# umodular_brain8_arduino_mega_rev01.net
KiCad netlist of a schematic drawn in EAGLE
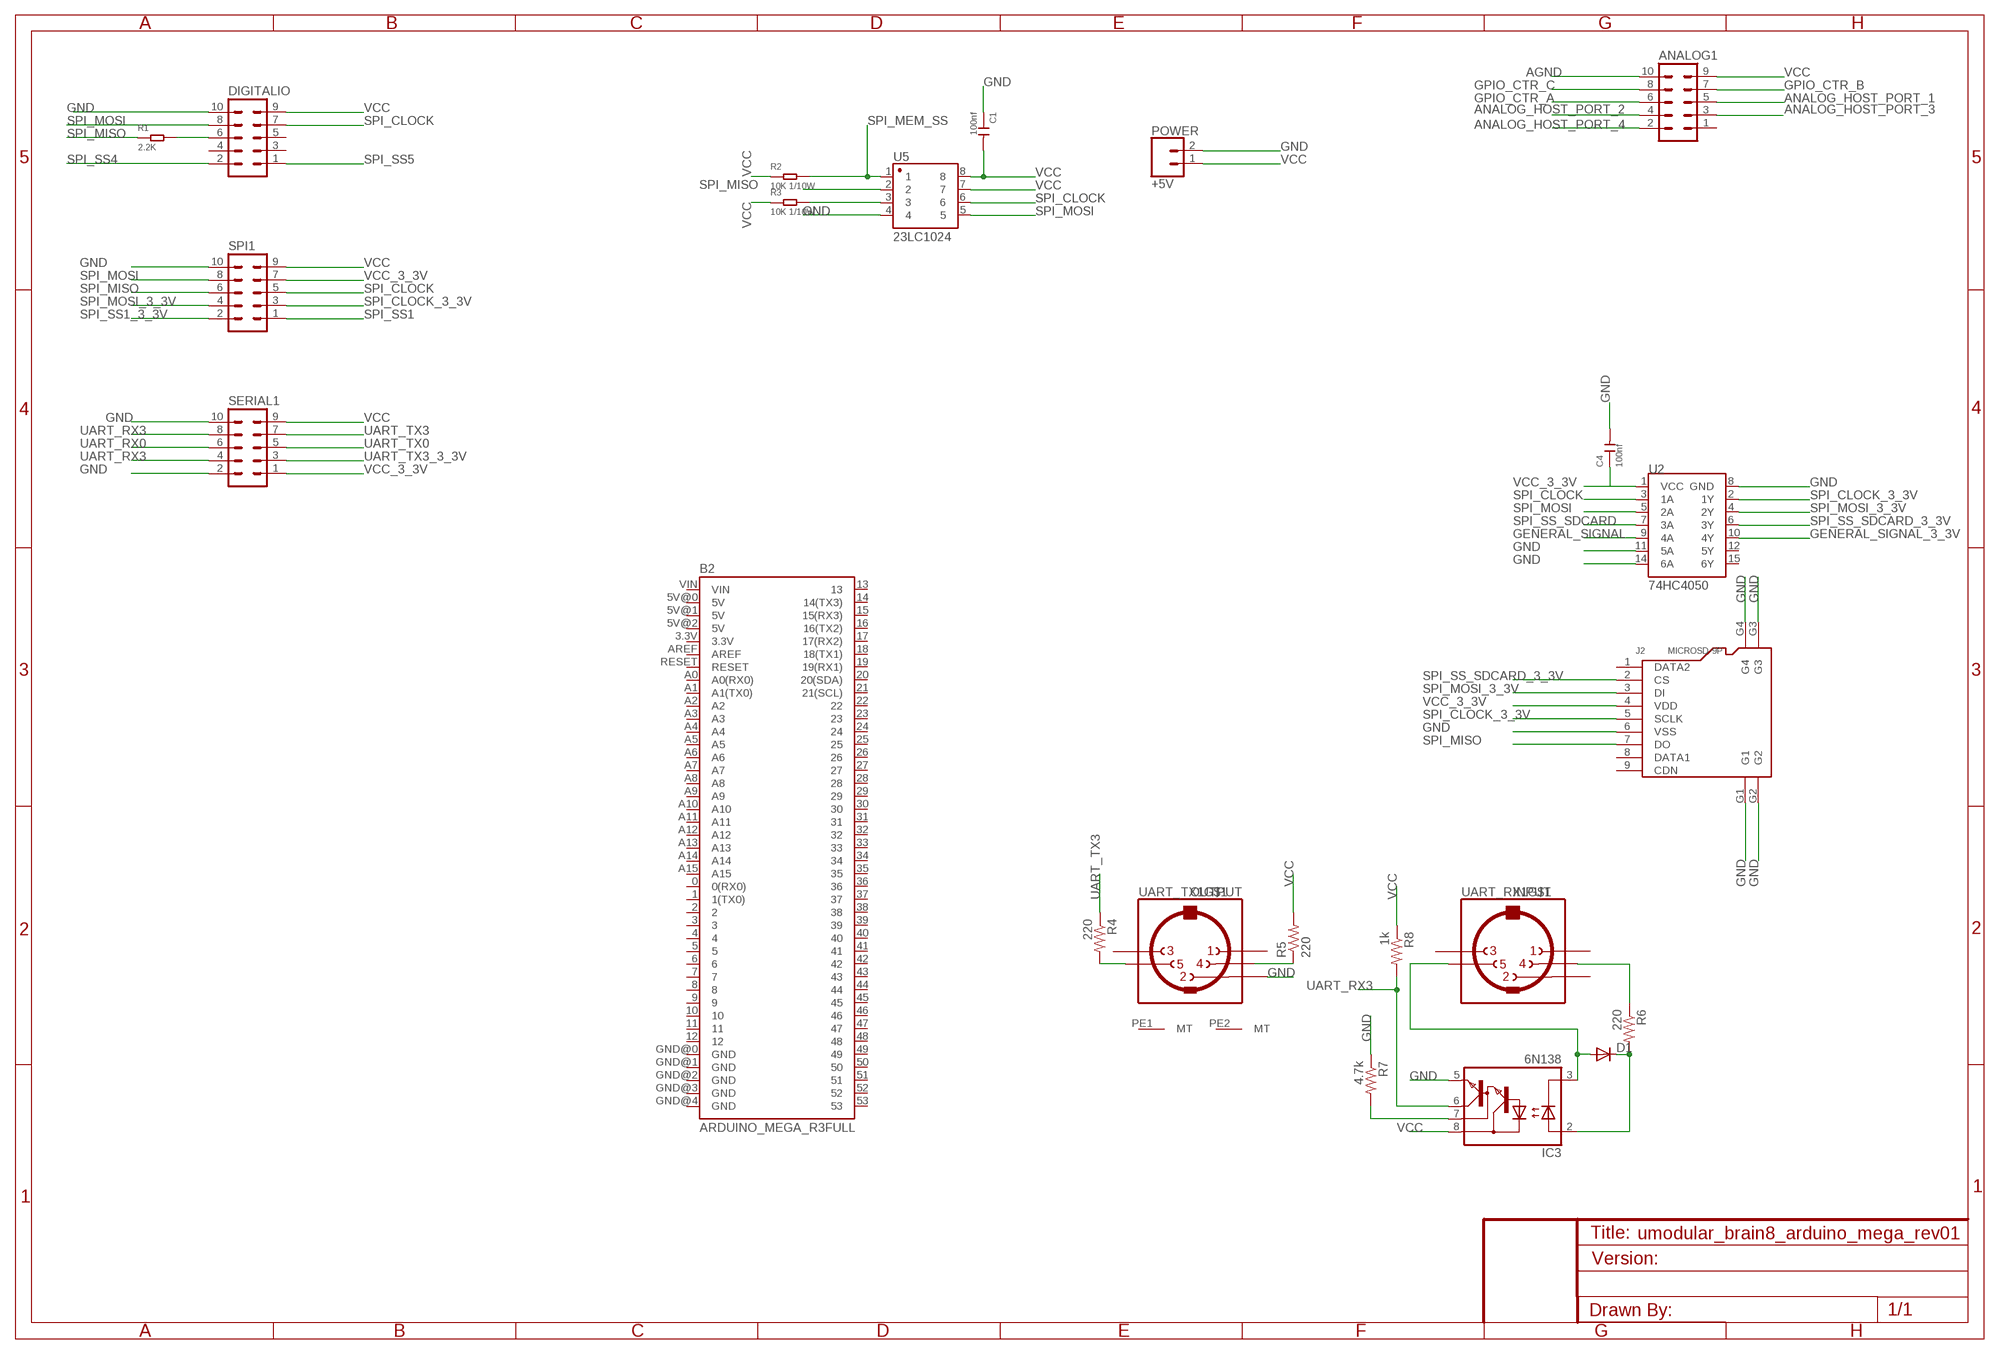
[diagram p0: schematic, sheet 1]

(export (version "E")
  (design (tool "Eeschema 10.0.6"))
  (components
    (comp (ref "ANALOG1")
      (value "MA05-2")
      (footprint "eagle-import:MA05-2")
      (libsource (lib "eagle-import") (part "MA05-2"))
    )
    (comp (ref "B2")
      (value "ARDUINO_MEGA_R3FULL")
      (footprint "eagle-import:ARDUINO_MEGA")
      (libsource (lib "eagle-import") (part "ARDUINO_MEGA_R3FULL"))
    )
    (comp (ref "C1")
      (value "100nf")
      (footprint "eagle-import:C0805")
      (fields (field (name "MPN") "CC0805KRX7R9BB104"))
      (libsource (lib "eagle-import") (part "CERAMIC-100NF-50V-10%-X7R(0805)"))
    )
    (comp (ref "C4")
      (value "100nf")
      (footprint "eagle-import:C0805")
      (fields (field (name "MPN") "CC0805KRX7R9BB104"))
      (libsource (lib "eagle-import") (part "CERAMIC-100NF-50V-10%-X7R(0805)"))
    )
    (comp (ref "D1")
      (value "1N4148DO35-7")
      (footprint "eagle-import:DO35-7")
      (libsource (lib "eagle-import") (part "1N4148DO35-7"))
    )
    (comp (ref "DIGITALIO")
      (value "MA05-2")
      (footprint "eagle-import:MA05-2")
      (libsource (lib "eagle-import") (part "MA05-2"))
    )
    (comp (ref "IC3")
      (value "6N138")
      (footprint "eagle-import:DIL08")
      (fields (field (name "MF") "VISHAY/TELEFUNKEN"))
      (libsource (lib "eagle-import") (part "6N138"))
    )
    (comp (ref "J2")
      (value "MICROSD-9P")
      (footprint "eagle-import:MICRO-SD9+4P-SMD-16.1X14.5X1.85MM")
      (libsource (lib "eagle-import") (part "MICRO-SD-CARD-HOLDER-9P"))
    )
    (comp (ref "POWER")
      (value "+5V")
      (footprint "eagle-import:1X02_LOCK_LONGPADS")
      (libsource (lib "eagle-import") (part "CONN_02LOCK_LONGPADS"))
    )
    (comp (ref "R1")
      (value "2.2K")
      (footprint "eagle-import:R0603")
      (fields (field (name "MPN") "RC0603JR-072K2L"))
      (libsource (lib "eagle-import") (part "SMD-RES-2.2K-5%-1/10W(0603)"))
    )
    (comp (ref "R2")
      (value "10K 1/10W")
      (footprint "eagle-import:R0603")
      (fields (field (name "MPN") "RC0603JR-0710KL"))
      (libsource (lib "eagle-import") (part "SMD-RES-10K-5%-1/10W(0603)"))
    )
    (comp (ref "R3")
      (value "10K 1/10W")
      (footprint "eagle-import:R0603")
      (fields (field (name "MPN") "RC0603JR-0710KL"))
      (libsource (lib "eagle-import") (part "SMD-RES-10K-5%-1/10W(0603)"))
    )
    (comp (ref "R4")
      (value "220")
      (footprint "eagle-import:0204_7@1")
      (libsource (lib "eagle-import") (part "R-US_0204/7"))
    )
    (comp (ref "R5")
      (value "220")
      (footprint "eagle-import:0204_7@1")
      (libsource (lib "eagle-import") (part "R-US_0204/7"))
    )
    (comp (ref "R6")
      (value "220")
      (footprint "eagle-import:0204_7@1")
      (libsource (lib "eagle-import") (part "R-US_0204/7"))
    )
    (comp (ref "R7")
      (value "4.7k")
      (footprint "eagle-import:0204_7@1")
      (libsource (lib "eagle-import") (part "R-US_0204/7"))
    )
    (comp (ref "R8")
      (value "1k")
      (footprint "eagle-import:0204_7@1")
      (libsource (lib "eagle-import") (part "R-US_0204/7"))
    )
    (comp (ref "SERIAL1")
      (value "MA05-2")
      (footprint "eagle-import:MA05-2")
      (libsource (lib "eagle-import") (part "MA05-2"))
    )
    (comp (ref "SPI1")
      (value "MA05-2")
      (footprint "eagle-import:MA05-2")
      (libsource (lib "eagle-import") (part "MA05-2"))
    )
    (comp (ref "U2")
      (value "74HC4050")
      (footprint "eagle-import:SO16")
      (libsource (lib "eagle-import") (part "HEX_CONVERTER"))
    )
    (comp (ref "U5")
      (value "23LC1024")
      (footprint "eagle-import:SO08")
      (libsource (lib "eagle-import") (part "GENERIC-SOIC8MSGEQ7N-FILTER"))
    )
    (comp (ref "UART_RX1")
      (value "INPUT")
      (footprint "eagle-import:CP-2350")
      (libsource (lib "eagle-import") (part "MIDIJACK"))
    )
    (comp (ref "UART_TX1")
      (value "OUTPUT")
      (footprint "eagle-import:CP-2350")
      (libsource (lib "eagle-import") (part "MIDIJACK"))
    )
  )
  (nets
    (net (code "1") (name "/AGND") (class "Default")
      (node (ref "ANALOG1") (pin "10") (pinfunction "10_10") (pintype "passive"))
    )
    (net (code "2") (name "/ANALOG_HOST_PORT_1") (class "Default")
      (node (ref "ANALOG1") (pin "5") (pinfunction "5_5") (pintype "passive"))
    )
    (net (code "3") (name "/ANALOG_HOST_PORT_2") (class "Default")
      (node (ref "ANALOG1") (pin "4") (pinfunction "4_4") (pintype "passive"))
    )
    (net (code "4") (name "/ANALOG_HOST_PORT_3") (class "Default")
      (node (ref "ANALOG1") (pin "3") (pinfunction "3_3") (pintype "passive"))
    )
    (net (code "5") (name "/ANALOG_HOST_PORT_4") (class "Default")
      (node (ref "ANALOG1") (pin "2") (pinfunction "2_2") (pintype "passive"))
    )
    (net (code "6") (name "/GENERAL_SIGNAL") (class "Default")
      (node (ref "U2") (pin "9") (pinfunction "4A_9") (pintype "bidirectional"))
    )
    (net (code "7") (name "/GENERAL_SIGNAL_3_3V") (class "Default")
      (node (ref "U2") (pin "10") (pinfunction "4Y_10") (pintype "bidirectional"))
    )
    (net (code "8") (name "/GND") (class "Default")
      (node (ref "C1") (pin "1") (pinfunction "1_1") (pintype "passive"))
      (node (ref "C4") (pin "2") (pinfunction "2_2") (pintype "passive"))
      (node (ref "DIGITALIO") (pin "10") (pinfunction "10_10") (pintype "passive"))
      (node (ref "IC3") (pin "5") (pinfunction "GND_5") (pintype "passive"))
      (node (ref "J2") (pin "6") (pinfunction "VSS_6") (pintype "bidirectional"))
      (node (ref "J2") (pin "G1") (pinfunction "G1_G1") (pintype "bidirectional"))
      (node (ref "J2") (pin "G2") (pinfunction "G2_G2") (pintype "bidirectional"))
      (node (ref "J2") (pin "G3") (pinfunction "G3_G3") (pintype "bidirectional"))
      (node (ref "J2") (pin "G4") (pinfunction "G4_G4") (pintype "bidirectional"))
      (node (ref "POWER") (pin "2") (pinfunction "2_2") (pintype "passive"))
      (node (ref "R7") (pin "1") (pinfunction "1_1") (pintype "passive"))
      (node (ref "SERIAL1") (pin "10") (pinfunction "10_10") (pintype "passive"))
      (node (ref "SERIAL1") (pin "2") (pinfunction "2_2") (pintype "passive"))
      (node (ref "SPI1") (pin "10") (pinfunction "10_10") (pintype "passive"))
      (node (ref "U2") (pin "11") (pinfunction "5A_11") (pintype "bidirectional"))
      (node (ref "U2") (pin "14") (pinfunction "6A_14") (pintype "bidirectional"))
      (node (ref "U2") (pin "8") (pinfunction "GND_8") (pintype "bidirectional"))
      (node (ref "U5") (pin "4") (pinfunction "4_4") (pintype "bidirectional"))
      (node (ref "UART_TX1") (pin "2") (pinfunction "2_2") (pintype "passive"))
    )
    (net (code "9") (name "/GPIO_CTR_A") (class "Default")
      (node (ref "ANALOG1") (pin "6") (pinfunction "6_6") (pintype "passive"))
    )
    (net (code "10") (name "/GPIO_CTR_B") (class "Default")
      (node (ref "ANALOG1") (pin "7") (pinfunction "7_7") (pintype "passive"))
    )
    (net (code "11") (name "/GPIO_CTR_C") (class "Default")
      (node (ref "ANALOG1") (pin "8") (pinfunction "8_8") (pintype "passive"))
    )
    (net (code "12") (name "/SPI_CLOCK") (class "Default")
      (node (ref "DIGITALIO") (pin "7") (pinfunction "7_7") (pintype "passive"))
      (node (ref "SPI1") (pin "5") (pinfunction "5_5") (pintype "passive"))
      (node (ref "U2") (pin "3") (pinfunction "1A_3") (pintype "bidirectional"))
      (node (ref "U5") (pin "6") (pinfunction "6_6") (pintype "bidirectional"))
    )
    (net (code "13") (name "/SPI_CLOCK_3_3V") (class "Default")
      (node (ref "J2") (pin "5") (pinfunction "SCLK_5") (pintype "bidirectional"))
      (node (ref "SPI1") (pin "3") (pinfunction "3_3") (pintype "passive"))
      (node (ref "U2") (pin "2") (pinfunction "1Y_2") (pintype "bidirectional"))
    )
    (net (code "14") (name "/SPI_MEM_SS") (class "Default")
      (node (ref "R2") (pin "2") (pinfunction "2_2") (pintype "passive"))
      (node (ref "U5") (pin "1") (pinfunction "1_1") (pintype "bidirectional"))
    )
    (net (code "15") (name "/SPI_MISO") (class "Default")
      (node (ref "J2") (pin "7") (pinfunction "DO_7") (pintype "bidirectional"))
      (node (ref "R1") (pin "1") (pinfunction "1_1") (pintype "passive"))
      (node (ref "SPI1") (pin "6") (pinfunction "6_6") (pintype "passive"))
      (node (ref "U5") (pin "2") (pinfunction "2_2") (pintype "bidirectional"))
    )
    (net (code "16") (name "/SPI_MOSI") (class "Default")
      (node (ref "DIGITALIO") (pin "8") (pinfunction "8_8") (pintype "passive"))
      (node (ref "SPI1") (pin "8") (pinfunction "8_8") (pintype "passive"))
      (node (ref "U2") (pin "5") (pinfunction "2A_5") (pintype "bidirectional"))
      (node (ref "U5") (pin "5") (pinfunction "5_5") (pintype "bidirectional"))
    )
    (net (code "17") (name "/SPI_MOSI_3_3V") (class "Default")
      (node (ref "J2") (pin "3") (pinfunction "DI_3") (pintype "bidirectional"))
      (node (ref "SPI1") (pin "4") (pinfunction "4_4") (pintype "passive"))
      (node (ref "U2") (pin "4") (pinfunction "2Y_4") (pintype "bidirectional"))
    )
    (net (code "18") (name "/SPI_SS1") (class "Default")
      (node (ref "SPI1") (pin "1") (pinfunction "1_1") (pintype "passive"))
    )
    (net (code "19") (name "/SPI_SS1_3_3V") (class "Default")
      (node (ref "SPI1") (pin "2") (pinfunction "2_2") (pintype "passive"))
    )
    (net (code "20") (name "/SPI_SS4") (class "Default")
      (node (ref "DIGITALIO") (pin "2") (pinfunction "2_2") (pintype "passive"))
    )
    (net (code "21") (name "/SPI_SS5") (class "Default")
      (node (ref "DIGITALIO") (pin "1") (pinfunction "1_1") (pintype "passive"))
    )
    (net (code "22") (name "/SPI_SS_SDCARD") (class "Default")
      (node (ref "U2") (pin "7") (pinfunction "3A_7") (pintype "bidirectional"))
    )
    (net (code "23") (name "/SPI_SS_SDCARD_3_3V") (class "Default")
      (node (ref "J2") (pin "2") (pinfunction "CS_2") (pintype "bidirectional"))
      (node (ref "U2") (pin "6") (pinfunction "3Y_6") (pintype "bidirectional"))
    )
    (net (code "24") (name "/UART_RX0") (class "Default")
      (node (ref "SERIAL1") (pin "6") (pinfunction "6_6") (pintype "passive"))
    )
    (net (code "25") (name "/UART_RX3") (class "Default")
      (node (ref "IC3") (pin "6") (pinfunction "VO_6") (pintype "passive"))
      (node (ref "R8") (pin "2") (pinfunction "2_2") (pintype "passive"))
      (node (ref "SERIAL1") (pin "4") (pinfunction "4_4") (pintype "passive"))
      (node (ref "SERIAL1") (pin "8") (pinfunction "8_8") (pintype "passive"))
    )
    (net (code "26") (name "/UART_TX0") (class "Default")
      (node (ref "SERIAL1") (pin "5") (pinfunction "5_5") (pintype "passive"))
    )
    (net (code "27") (name "/UART_TX3") (class "Default")
      (node (ref "R4") (pin "1") (pinfunction "1_1") (pintype "passive"))
      (node (ref "SERIAL1") (pin "7") (pinfunction "7_7") (pintype "passive"))
    )
    (net (code "28") (name "/UART_TX3_3_3V") (class "Default")
      (node (ref "SERIAL1") (pin "3") (pinfunction "3_3") (pintype "passive"))
    )
    (net (code "29") (name "/VCC") (class "Default")
      (node (ref "ANALOG1") (pin "9") (pinfunction "9_9") (pintype "passive"))
      (node (ref "C1") (pin "2") (pinfunction "2_2") (pintype "passive"))
      (node (ref "DIGITALIO") (pin "9") (pinfunction "9_9") (pintype "passive"))
      (node (ref "IC3") (pin "8") (pinfunction "VCC_8") (pintype "passive"))
      (node (ref "POWER") (pin "1") (pinfunction "1_1") (pintype "passive"))
      (node (ref "R2") (pin "1") (pinfunction "1_1") (pintype "passive"))
      (node (ref "R3") (pin "1") (pinfunction "1_1") (pintype "passive"))
      (node (ref "R5") (pin "2") (pinfunction "2_2") (pintype "passive"))
      (node (ref "R8") (pin "1") (pinfunction "1_1") (pintype "passive"))
      (node (ref "SERIAL1") (pin "9") (pinfunction "9_9") (pintype "passive"))
      (node (ref "SPI1") (pin "9") (pinfunction "9_9") (pintype "passive"))
      (node (ref "U5") (pin "7") (pinfunction "7_7") (pintype "bidirectional"))
      (node (ref "U5") (pin "8") (pinfunction "8_8") (pintype "bidirectional"))
    )
    (net (code "30") (name "/VCC_3_3V") (class "Default")
      (node (ref "C4") (pin "1") (pinfunction "1_1") (pintype "passive"))
      (node (ref "J2") (pin "4") (pinfunction "VDD_4") (pintype "bidirectional"))
      (node (ref "SERIAL1") (pin "1") (pinfunction "1_1") (pintype "passive"))
      (node (ref "SPI1") (pin "7") (pinfunction "7_7") (pintype "passive"))
      (node (ref "U2") (pin "1") (pinfunction "VCC_1") (pintype "bidirectional"))
    )
    (net (code "31") (name "Net-(DIGITALIO-Pad6)") (class "Default")
      (node (ref "DIGITALIO") (pin "6") (pinfunction "6_6") (pintype "passive"))
      (node (ref "R1") (pin "2") (pinfunction "2_2") (pintype "passive"))
    )
    (net (code "32") (name "Net-(IC3-A)") (class "Default")
      (node (ref "D1") (pin "C") (pinfunction "C_C") (pintype "passive"))
      (node (ref "IC3") (pin "2") (pinfunction "A_2") (pintype "passive"))
      (node (ref "R6") (pin "2") (pinfunction "2_2") (pintype "passive"))
    )
    (net (code "33") (name "Net-(IC3-C)") (class "Default")
      (node (ref "D1") (pin "A") (pinfunction "A_A") (pintype "passive"))
      (node (ref "IC3") (pin "3") (pinfunction "C_3") (pintype "passive"))
      (node (ref "UART_RX1") (pin "5") (pinfunction "5_5") (pintype "passive"))
    )
    (net (code "34") (name "Net-(IC3-VB)") (class "Default")
      (node (ref "IC3") (pin "7") (pinfunction "VB_7") (pintype "passive"))
      (node (ref "R7") (pin "2") (pinfunction "2_2") (pintype "passive"))
    )
    (net (code "35") (name "Net-(R3-Pad2)") (class "Default")
      (node (ref "R3") (pin "2") (pinfunction "2_2") (pintype "passive"))
      (node (ref "U5") (pin "3") (pinfunction "3_3") (pintype "bidirectional"))
    )
    (net (code "36") (name "Net-(R4-Pad2)") (class "Default")
      (node (ref "R4") (pin "2") (pinfunction "2_2") (pintype "passive"))
      (node (ref "UART_TX1") (pin "5") (pinfunction "5_5") (pintype "passive"))
    )
    (net (code "37") (name "Net-(R5-Pad1)") (class "Default")
      (node (ref "R5") (pin "1") (pinfunction "1_1") (pintype "passive"))
      (node (ref "UART_TX1") (pin "4") (pinfunction "4_4") (pintype "passive"))
    )
    (net (code "38") (name "Net-(R6-Pad1)") (class "Default")
      (node (ref "R6") (pin "1") (pinfunction "1_1") (pintype "passive"))
      (node (ref "UART_RX1") (pin "4") (pinfunction "4_4") (pintype "passive"))
    )
    (net (code "39") (name "unconnected-(ANALOG1-Pad1)") (class "Default")
      (node (ref "ANALOG1") (pin "1") (pinfunction "1_1") (pintype "passive"))
    )
    (net (code "40") (name "unconnected-(B2-0(RX0)-Pad0)") (class "Default")
      (node (ref "B2") (pin "0") (pinfunction "0(RX0)_0") (pintype "bidirectional"))
    )
    (net (code "41") (name "unconnected-(B2-1(TX0)-Pad1)") (class "Default")
      (node (ref "B2") (pin "1") (pinfunction "1(TX0)_1") (pintype "bidirectional"))
    )
    (net (code "42") (name "unconnected-(B2-5V-Pad5V@0)") (class "Default")
      (node (ref "B2") (pin "5V@0") (pinfunction "5V_5V@0") (pintype "bidirectional"))
    )
    (net (code "43") (name "unconnected-(B2-5V-Pad5V@1)") (class "Default")
      (node (ref "B2") (pin "5V@1") (pinfunction "5V_5V@1") (pintype "bidirectional"))
    )
    (net (code "44") (name "unconnected-(B2-5V-Pad5V@2)") (class "Default")
      (node (ref "B2") (pin "5V@2") (pinfunction "5V_5V@2") (pintype "bidirectional"))
    )
    (net (code "45") (name "unconnected-(B2-14(TX3)-Pad14)") (class "Default")
      (node (ref "B2") (pin "14") (pinfunction "14(TX3)_14") (pintype "bidirectional"))
    )
    (net (code "46") (name "unconnected-(B2-15(RX3)-Pad15)") (class "Default")
      (node (ref "B2") (pin "15") (pinfunction "15(RX3)_15") (pintype "bidirectional"))
    )
    (net (code "47") (name "unconnected-(B2-16(TX2)-Pad16)") (class "Default")
      (node (ref "B2") (pin "16") (pinfunction "16(TX2)_16") (pintype "bidirectional"))
    )
    (net (code "48") (name "unconnected-(B2-17(RX2)-Pad17)") (class "Default")
      (node (ref "B2") (pin "17") (pinfunction "17(RX2)_17") (pintype "bidirectional"))
    )
    (net (code "49") (name "unconnected-(B2-18(TX1)-Pad18)") (class "Default")
      (node (ref "B2") (pin "18") (pinfunction "18(TX1)_18") (pintype "bidirectional"))
    )
    (net (code "50") (name "unconnected-(B2-19(RX1)-Pad19)") (class "Default")
      (node (ref "B2") (pin "19") (pinfunction "19(RX1)_19") (pintype "bidirectional"))
    )
    (net (code "51") (name "unconnected-(B2-20(SDA)-Pad20)") (class "Default")
      (node (ref "B2") (pin "20") (pinfunction "20(SDA)_20") (pintype "bidirectional"))
    )
    (net (code "52") (name "unconnected-(B2-21(SCL)-Pad21)") (class "Default")
      (node (ref "B2") (pin "21") (pinfunction "21(SCL)_21") (pintype "bidirectional"))
    )
    (net (code "53") (name "unconnected-(B2-A0(RX0)-PadA0)") (class "Default")
      (node (ref "B2") (pin "A0") (pinfunction "A0(RX0)_A0") (pintype "bidirectional"))
    )
    (net (code "54") (name "unconnected-(B2-A1(TX0)-PadA1)") (class "Default")
      (node (ref "B2") (pin "A1") (pinfunction "A1(TX0)_A1") (pintype "bidirectional"))
    )
    (net (code "55") (name "unconnected-(B2-GND-PadGND@0)") (class "Default")
      (node (ref "B2") (pin "GND@0") (pinfunction "GND_GND@0") (pintype "bidirectional"))
    )
    (net (code "56") (name "unconnected-(B2-GND-PadGND@1)") (class "Default")
      (node (ref "B2") (pin "GND@1") (pinfunction "GND_GND@1") (pintype "bidirectional"))
    )
    (net (code "57") (name "unconnected-(B2-GND-PadGND@2)") (class "Default")
      (node (ref "B2") (pin "GND@2") (pinfunction "GND_GND@2") (pintype "bidirectional"))
    )
    (net (code "58") (name "unconnected-(B2-GND-PadGND@3)") (class "Default")
      (node (ref "B2") (pin "GND@3") (pinfunction "GND_GND@3") (pintype "bidirectional"))
    )
    (net (code "59") (name "unconnected-(B2-GND-PadGND@4)") (class "Default")
      (node (ref "B2") (pin "GND@4") (pinfunction "GND_GND@4") (pintype "bidirectional"))
    )
    (net (code "60") (name "unconnected-(B2-Pad2)") (class "Default")
      (node (ref "B2") (pin "2") (pinfunction "2_2") (pintype "bidirectional"))
    )
    (net (code "61") (name "unconnected-(B2-Pad3)") (class "Default")
      (node (ref "B2") (pin "3") (pinfunction "3_3") (pintype "bidirectional"))
    )
    (net (code "62") (name "unconnected-(B2-Pad3.3V)") (class "Default")
      (node (ref "B2") (pin "3.3V") (pinfunction "3.3V_3.3V") (pintype "bidirectional"))
    )
    (net (code "63") (name "unconnected-(B2-Pad4)") (class "Default")
      (node (ref "B2") (pin "4") (pinfunction "4_4") (pintype "bidirectional"))
    )
    (net (code "64") (name "unconnected-(B2-Pad5)") (class "Default")
      (node (ref "B2") (pin "5") (pinfunction "5_5") (pintype "bidirectional"))
    )
    (net (code "65") (name "unconnected-(B2-Pad6)") (class "Default")
      (node (ref "B2") (pin "6") (pinfunction "6_6") (pintype "bidirectional"))
    )
    (net (code "66") (name "unconnected-(B2-Pad7)") (class "Default")
      (node (ref "B2") (pin "7") (pinfunction "7_7") (pintype "bidirectional"))
    )
    (net (code "67") (name "unconnected-(B2-Pad8)") (class "Default")
      (node (ref "B2") (pin "8") (pinfunction "8_8") (pintype "bidirectional"))
    )
    (net (code "68") (name "unconnected-(B2-Pad9)") (class "Default")
      (node (ref "B2") (pin "9") (pinfunction "9_9") (pintype "bidirectional"))
    )
    (net (code "69") (name "unconnected-(B2-Pad10)") (class "Default")
      (node (ref "B2") (pin "10") (pinfunction "10_10") (pintype "bidirectional"))
    )
    (net (code "70") (name "unconnected-(B2-Pad11)") (class "Default")
      (node (ref "B2") (pin "11") (pinfunction "11_11") (pintype "bidirectional"))
    )
    (net (code "71") (name "unconnected-(B2-Pad12)") (class "Default")
      (node (ref "B2") (pin "12") (pinfunction "12_12") (pintype "bidirectional"))
    )
    (net (code "72") (name "unconnected-(B2-Pad13)") (class "Default")
      (node (ref "B2") (pin "13") (pinfunction "13_13") (pintype "bidirectional"))
    )
    (net (code "73") (name "unconnected-(B2-Pad22)") (class "Default")
      (node (ref "B2") (pin "22") (pinfunction "22_22") (pintype "bidirectional"))
    )
    (net (code "74") (name "unconnected-(B2-Pad23)") (class "Default")
      (node (ref "B2") (pin "23") (pinfunction "23_23") (pintype "bidirectional"))
    )
    (net (code "75") (name "unconnected-(B2-Pad24)") (class "Default")
      (node (ref "B2") (pin "24") (pinfunction "24_24") (pintype "bidirectional"))
    )
    (net (code "76") (name "unconnected-(B2-Pad25)") (class "Default")
      (node (ref "B2") (pin "25") (pinfunction "25_25") (pintype "bidirectional"))
    )
    (net (code "77") (name "unconnected-(B2-Pad26)") (class "Default")
      (node (ref "B2") (pin "26") (pinfunction "26_26") (pintype "bidirectional"))
    )
    (net (code "78") (name "unconnected-(B2-Pad27)") (class "Default")
      (node (ref "B2") (pin "27") (pinfunction "27_27") (pintype "bidirectional"))
    )
    (net (code "79") (name "unconnected-(B2-Pad28)") (class "Default")
      (node (ref "B2") (pin "28") (pinfunction "28_28") (pintype "bidirectional"))
    )
    (net (code "80") (name "unconnected-(B2-Pad29)") (class "Default")
      (node (ref "B2") (pin "29") (pinfunction "29_29") (pintype "bidirectional"))
    )
    (net (code "81") (name "unconnected-(B2-Pad30)") (class "Default")
      (node (ref "B2") (pin "30") (pinfunction "30_30") (pintype "bidirectional"))
    )
    (net (code "82") (name "unconnected-(B2-Pad31)") (class "Default")
      (node (ref "B2") (pin "31") (pinfunction "31_31") (pintype "bidirectional"))
    )
    (net (code "83") (name "unconnected-(B2-Pad32)") (class "Default")
      (node (ref "B2") (pin "32") (pinfunction "32_32") (pintype "bidirectional"))
    )
    (net (code "84") (name "unconnected-(B2-Pad33)") (class "Default")
      (node (ref "B2") (pin "33") (pinfunction "33_33") (pintype "bidirectional"))
    )
    (net (code "85") (name "unconnected-(B2-Pad34)") (class "Default")
      (node (ref "B2") (pin "34") (pinfunction "34_34") (pintype "bidirectional"))
    )
    (net (code "86") (name "unconnected-(B2-Pad35)") (class "Default")
      (node (ref "B2") (pin "35") (pinfunction "35_35") (pintype "bidirectional"))
    )
    (net (code "87") (name "unconnected-(B2-Pad36)") (class "Default")
      (node (ref "B2") (pin "36") (pinfunction "36_36") (pintype "bidirectional"))
    )
    (net (code "88") (name "unconnected-(B2-Pad37)") (class "Default")
      (node (ref "B2") (pin "37") (pinfunction "37_37") (pintype "bidirectional"))
    )
    (net (code "89") (name "unconnected-(B2-Pad38)") (class "Default")
      (node (ref "B2") (pin "38") (pinfunction "38_38") (pintype "bidirectional"))
    )
    (net (code "90") (name "unconnected-(B2-Pad39)") (class "Default")
      (node (ref "B2") (pin "39") (pinfunction "39_39") (pintype "bidirectional"))
    )
    (net (code "91") (name "unconnected-(B2-Pad40)") (class "Default")
      (node (ref "B2") (pin "40") (pinfunction "40_40") (pintype "bidirectional"))
    )
    (net (code "92") (name "unconnected-(B2-Pad41)") (class "Default")
      (node (ref "B2") (pin "41") (pinfunction "41_41") (pintype "bidirectional"))
    )
    (net (code "93") (name "unconnected-(B2-Pad42)") (class "Default")
      (node (ref "B2") (pin "42") (pinfunction "42_42") (pintype "bidirectional"))
    )
    (net (code "94") (name "unconnected-(B2-Pad43)") (class "Default")
      (node (ref "B2") (pin "43") (pinfunction "43_43") (pintype "bidirectional"))
    )
    (net (code "95") (name "unconnected-(B2-Pad44)") (class "Default")
      (node (ref "B2") (pin "44") (pinfunction "44_44") (pintype "bidirectional"))
    )
    (net (code "96") (name "unconnected-(B2-Pad45)") (class "Default")
      (node (ref "B2") (pin "45") (pinfunction "45_45") (pintype "bidirectional"))
    )
    (net (code "97") (name "unconnected-(B2-Pad46)") (class "Default")
      (node (ref "B2") (pin "46") (pinfunction "46_46") (pintype "bidirectional"))
    )
    (net (code "98") (name "unconnected-(B2-Pad47)") (class "Default")
      (node (ref "B2") (pin "47") (pinfunction "47_47") (pintype "bidirectional"))
    )
    (net (code "99") (name "unconnected-(B2-Pad48)") (class "Default")
      (node (ref "B2") (pin "48") (pinfunction "48_48") (pintype "bidirectional"))
    )
    (net (code "100") (name "unconnected-(B2-Pad49)") (class "Default")
      (node (ref "B2") (pin "49") (pinfunction "49_49") (pintype "bidirectional"))
    )
    (net (code "101") (name "unconnected-(B2-Pad50)") (class "Default")
      (node (ref "B2") (pin "50") (pinfunction "50_50") (pintype "bidirectional"))
    )
    (net (code "102") (name "unconnected-(B2-Pad51)") (class "Default")
      (node (ref "B2") (pin "51") (pinfunction "51_51") (pintype "bidirectional"))
    )
    (net (code "103") (name "unconnected-(B2-Pad52)") (class "Default")
      (node (ref "B2") (pin "52") (pinfunction "52_52") (pintype "bidirectional"))
    )
    (net (code "104") (name "unconnected-(B2-Pad53)") (class "Default")
      (node (ref "B2") (pin "53") (pinfunction "53_53") (pintype "bidirectional"))
    )
    (net (code "105") (name "unconnected-(B2-PadA2)") (class "Default")
      (node (ref "B2") (pin "A2") (pinfunction "A2_A2") (pintype "bidirectional"))
    )
    (net (code "106") (name "unconnected-(B2-PadA3)") (class "Default")
      (node (ref "B2") (pin "A3") (pinfunction "A3_A3") (pintype "bidirectional"))
    )
    (net (code "107") (name "unconnected-(B2-PadA4)") (class "Default")
      (node (ref "B2") (pin "A4") (pinfunction "A4_A4") (pintype "bidirectional"))
    )
    (net (code "108") (name "unconnected-(B2-PadA5)") (class "Default")
      (node (ref "B2") (pin "A5") (pinfunction "A5_A5") (pintype "bidirectional"))
    )
    (net (code "109") (name "unconnected-(B2-PadA6)") (class "Default")
      (node (ref "B2") (pin "A6") (pinfunction "A6_A6") (pintype "bidirectional"))
    )
    (net (code "110") (name "unconnected-(B2-PadA7)") (class "Default")
      (node (ref "B2") (pin "A7") (pinfunction "A7_A7") (pintype "bidirectional"))
    )
    (net (code "111") (name "unconnected-(B2-PadA8)") (class "Default")
      (node (ref "B2") (pin "A8") (pinfunction "A8_A8") (pintype "bidirectional"))
    )
    (net (code "112") (name "unconnected-(B2-PadA9)") (class "Default")
      (node (ref "B2") (pin "A9") (pinfunction "A9_A9") (pintype "bidirectional"))
    )
    (net (code "113") (name "unconnected-(B2-PadA10)") (class "Default")
      (node (ref "B2") (pin "A10") (pinfunction "A10_A10") (pintype "bidirectional"))
    )
    (net (code "114") (name "unconnected-(B2-PadA11)") (class "Default")
      (node (ref "B2") (pin "A11") (pinfunction "A11_A11") (pintype "bidirectional"))
    )
    (net (code "115") (name "unconnected-(B2-PadA12)") (class "Default")
      (node (ref "B2") (pin "A12") (pinfunction "A12_A12") (pintype "bidirectional"))
    )
    (net (code "116") (name "unconnected-(B2-PadA13)") (class "Default")
      (node (ref "B2") (pin "A13") (pinfunction "A13_A13") (pintype "bidirectional"))
    )
    (net (code "117") (name "unconnected-(B2-PadA14)") (class "Default")
      (node (ref "B2") (pin "A14") (pinfunction "A14_A14") (pintype "bidirectional"))
    )
    (net (code "118") (name "unconnected-(B2-PadA15)") (class "Default")
      (node (ref "B2") (pin "A15") (pinfunction "A15_A15") (pintype "bidirectional"))
    )
    (net (code "119") (name "unconnected-(B2-PadAREF)") (class "Default")
      (node (ref "B2") (pin "AREF") (pinfunction "AREF_AREF") (pintype "bidirectional"))
    )
    (net (code "120") (name "unconnected-(B2-PadRESET)") (class "Default")
      (node (ref "B2") (pin "RESET") (pinfunction "RESET_RESET") (pintype "bidirectional"))
    )
    (net (code "121") (name "unconnected-(B2-PadVIN)") (class "Default")
      (node (ref "B2") (pin "VIN") (pinfunction "VIN_VIN") (pintype "bidirectional"))
    )
    (net (code "122") (name "unconnected-(DIGITALIO-Pad3)") (class "Default")
      (node (ref "DIGITALIO") (pin "3") (pinfunction "3_3") (pintype "passive"))
    )
    (net (code "123") (name "unconnected-(DIGITALIO-Pad4)") (class "Default")
      (node (ref "DIGITALIO") (pin "4") (pinfunction "4_4") (pintype "passive"))
    )
    (net (code "124") (name "unconnected-(DIGITALIO-Pad5)") (class "Default")
      (node (ref "DIGITALIO") (pin "5") (pinfunction "5_5") (pintype "passive"))
    )
    (net (code "125") (name "unconnected-(J2-CDN-Pad9)") (class "Default")
      (node (ref "J2") (pin "9") (pinfunction "CDN_9") (pintype "bidirectional"))
    )
    (net (code "126") (name "unconnected-(J2-DATA1-Pad8)") (class "Default")
      (node (ref "J2") (pin "8") (pinfunction "DATA1_8") (pintype "bidirectional"))
    )
    (net (code "127") (name "unconnected-(J2-DATA2-Pad1)") (class "Default")
      (node (ref "J2") (pin "1") (pinfunction "DATA2_1") (pintype "bidirectional"))
    )
    (net (code "128") (name "unconnected-(U2-5Y-Pad12)") (class "Default")
      (node (ref "U2") (pin "12") (pinfunction "5Y_12") (pintype "bidirectional"))
    )
    (net (code "129") (name "unconnected-(U2-6Y-Pad15)") (class "Default")
      (node (ref "U2") (pin "15") (pinfunction "6Y_15") (pintype "bidirectional"))
    )
    (net (code "130") (name "unconnected-(UART_RX1-Pad1)") (class "Default")
      (node (ref "UART_RX1") (pin "1") (pinfunction "1_1") (pintype "passive"))
    )
    (net (code "131") (name "unconnected-(UART_RX1-Pad2)") (class "Default")
      (node (ref "UART_RX1") (pin "2") (pinfunction "2_2") (pintype "passive"))
    )
    (net (code "132") (name "unconnected-(UART_RX1-Pad3)") (class "Default")
      (node (ref "UART_RX1") (pin "3") (pinfunction "3_3") (pintype "passive"))
    )
    (net (code "133") (name "unconnected-(UART_TX1-Pad1)") (class "Default")
      (node (ref "UART_TX1") (pin "1") (pinfunction "1_1") (pintype "passive"))
    )
    (net (code "134") (name "unconnected-(UART_TX1-Pad3)") (class "Default")
      (node (ref "UART_TX1") (pin "3") (pinfunction "3_3") (pintype "passive"))
    )
    (net (code "135") (name "unconnected-(UART_TX1D-MT-PadPE1)") (class "Default")
      (node (ref "UART_TX1") (pin "PE1") (pinfunction "MT_PE1") (pintype "passive"))
    )
    (net (code "136") (name "unconnected-(UART_TX1E-MT-PadPE2)") (class "Default")
      (node (ref "UART_TX1") (pin "PE2") (pinfunction "MT_PE2") (pintype "passive"))
    )
  )
)
